# centraldb9.net
KiCad netlist of a schematic drawn in EAGLE
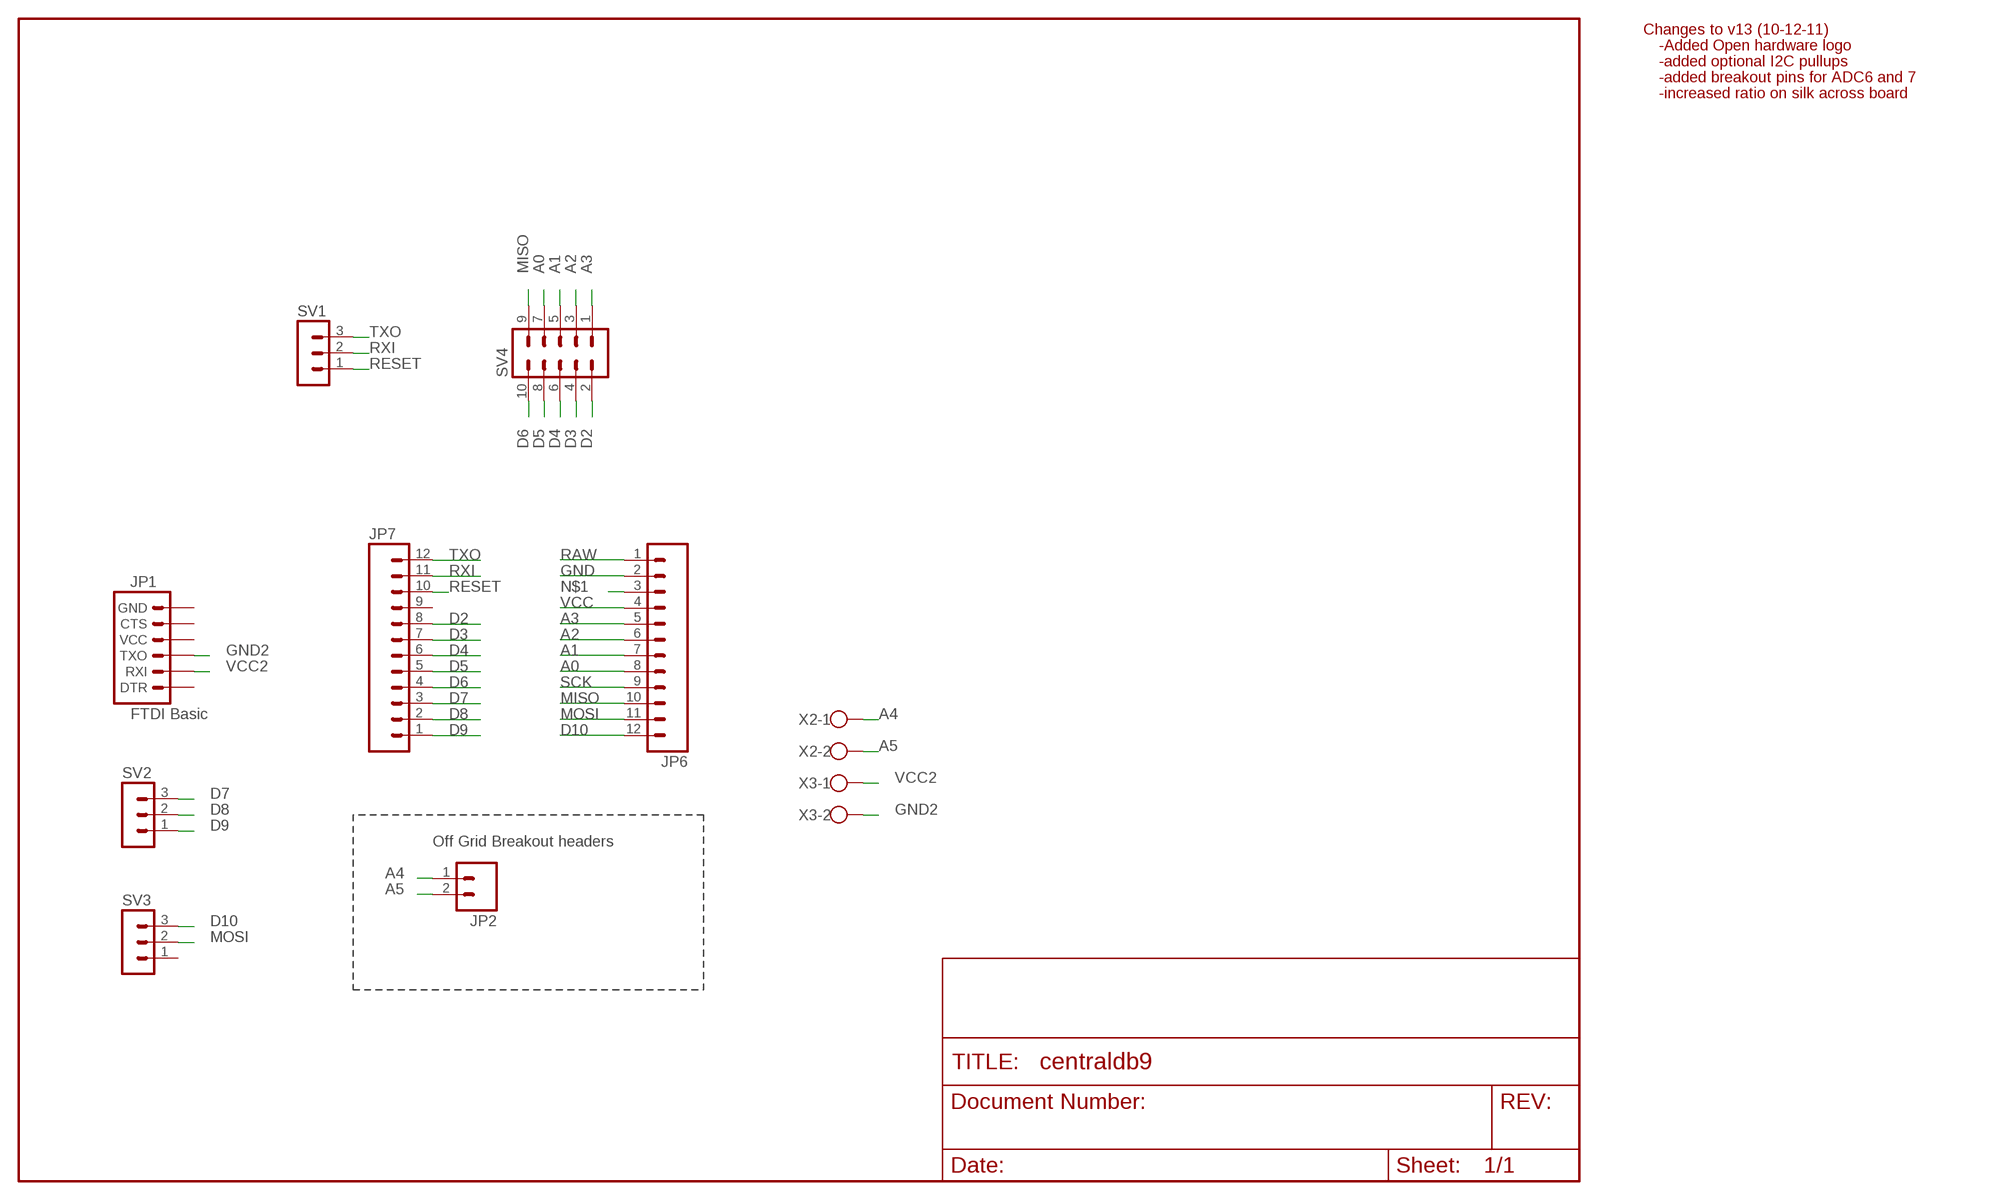
[diagram p0: schematic, sheet 1]

(export (version "E")
  (design (tool "Eeschema 10.0.6"))
  (components
    (comp (ref "JP1")
      (value "FTDI Basic")
      (footprint "eagle-import:1X06")
      (libsource (lib "eagle-import") (part "ARDUINO_SERIAL_PROGRAMPTH"))
    )
    (comp (ref "JP2")
      (value "M02PTH")
      (footprint "eagle-import:1X02")
      (libsource (lib "eagle-import") (part "M02PTH"))
    )
    (comp (ref "JP6")
      (value "M12PTH")
      (footprint "eagle-import:1X12")
      (libsource (lib "eagle-import") (part "M12PTH"))
    )
    (comp (ref "JP7")
      (value "M12PTH")
      (footprint "eagle-import:1X12")
      (libsource (lib "eagle-import") (part "M12PTH"))
    )
    (comp (ref "SV1")
      (value "MA03-1")
      (footprint "eagle-import:MA03-1")
      (libsource (lib "eagle-import") (part "MA03-1"))
    )
    (comp (ref "SV2")
      (value "MA03-1")
      (footprint "eagle-import:MA03-1")
      (libsource (lib "eagle-import") (part "MA03-1"))
    )
    (comp (ref "SV3")
      (value "MA03-1")
      (footprint "eagle-import:MA03-1")
      (libsource (lib "eagle-import") (part "MA03-1"))
    )
    (comp (ref "SV4")
      (value "MA05-2")
      (footprint "eagle-import:MA05-2")
      (libsource (lib "eagle-import") (part "MA05-2"))
    )
    (comp (ref "X2")
      (value "W237-102")
      (footprint "eagle-import:W237-102")
      (fields (field (name "MPN") "237-102"))
      (libsource (lib "eagle-import") (part "W237-102"))
    )
    (comp (ref "X3")
      (value "W237-102")
      (footprint "eagle-import:W237-102")
      (fields (field (name "MPN") "237-102"))
      (libsource (lib "eagle-import") (part "W237-102"))
    )
  )
  (nets
    (net (code "1") (name "/A0") (class "Default")
      (node (ref "JP6") (pin "8") (pinfunction "8_8") (pintype "passive"))
      (node (ref "SV4") (pin "7") (pinfunction "7_7") (pintype "passive"))
    )
    (net (code "2") (name "/A1") (class "Default")
      (node (ref "JP6") (pin "7") (pinfunction "7_7") (pintype "passive"))
      (node (ref "SV4") (pin "5") (pinfunction "5_5") (pintype "passive"))
    )
    (net (code "3") (name "/A2") (class "Default")
      (node (ref "JP6") (pin "6") (pinfunction "6_6") (pintype "passive"))
      (node (ref "SV4") (pin "3") (pinfunction "3_3") (pintype "passive"))
    )
    (net (code "4") (name "/A3") (class "Default")
      (node (ref "JP6") (pin "5") (pinfunction "5_5") (pintype "passive"))
      (node (ref "SV4") (pin "1") (pinfunction "1_1") (pintype "passive"))
    )
    (net (code "5") (name "/A4") (class "Default")
      (node (ref "JP2") (pin "1") (pinfunction "1_1") (pintype "passive"))
      (node (ref "X2") (pin "1") (pinfunction "KL_1") (pintype "passive"))
    )
    (net (code "6") (name "/A5") (class "Default")
      (node (ref "JP2") (pin "2") (pinfunction "2_2") (pintype "passive"))
      (node (ref "X2") (pin "2") (pinfunction "KL_2") (pintype "passive"))
    )
    (net (code "7") (name "/D2") (class "Default")
      (node (ref "JP7") (pin "8") (pinfunction "8_8") (pintype "passive"))
      (node (ref "SV4") (pin "2") (pinfunction "2_2") (pintype "passive"))
    )
    (net (code "8") (name "/D3") (class "Default")
      (node (ref "JP7") (pin "7") (pinfunction "7_7") (pintype "passive"))
      (node (ref "SV4") (pin "4") (pinfunction "4_4") (pintype "passive"))
    )
    (net (code "9") (name "/D4") (class "Default")
      (node (ref "JP7") (pin "6") (pinfunction "6_6") (pintype "passive"))
      (node (ref "SV4") (pin "6") (pinfunction "6_6") (pintype "passive"))
    )
    (net (code "10") (name "/D5") (class "Default")
      (node (ref "JP7") (pin "5") (pinfunction "5_5") (pintype "passive"))
      (node (ref "SV4") (pin "8") (pinfunction "8_8") (pintype "passive"))
    )
    (net (code "11") (name "/D6") (class "Default")
      (node (ref "JP7") (pin "4") (pinfunction "4_4") (pintype "passive"))
      (node (ref "SV4") (pin "10") (pinfunction "10_10") (pintype "passive"))
    )
    (net (code "12") (name "/D7") (class "Default")
      (node (ref "JP7") (pin "3") (pinfunction "3_3") (pintype "passive"))
      (node (ref "SV2") (pin "3") (pinfunction "3_3") (pintype "passive"))
    )
    (net (code "13") (name "/D8") (class "Default")
      (node (ref "JP7") (pin "2") (pinfunction "2_2") (pintype "passive"))
      (node (ref "SV2") (pin "2") (pinfunction "2_2") (pintype "passive"))
    )
    (net (code "14") (name "/D9") (class "Default")
      (node (ref "JP7") (pin "1") (pinfunction "1_1") (pintype "passive"))
      (node (ref "SV2") (pin "1") (pinfunction "1_1") (pintype "passive"))
    )
    (net (code "15") (name "/D10") (class "Default")
      (node (ref "JP6") (pin "12") (pinfunction "12_12") (pintype "passive"))
      (node (ref "SV3") (pin "3") (pinfunction "3_3") (pintype "passive"))
    )
    (net (code "16") (name "/GND") (class "Default")
      (node (ref "JP6") (pin "2") (pinfunction "2_2") (pintype "passive"))
    )
    (net (code "17") (name "/GND2") (class "Default")
      (node (ref "JP1") (pin "3") (pinfunction "TXO_3") (pintype "passive"))
      (node (ref "X3") (pin "2") (pinfunction "KL_2") (pintype "passive"))
    )
    (net (code "18") (name "/MISO") (class "Default")
      (node (ref "JP6") (pin "10") (pinfunction "10_10") (pintype "passive"))
      (node (ref "SV4") (pin "9") (pinfunction "9_9") (pintype "passive"))
    )
    (net (code "19") (name "/MOSI") (class "Default")
      (node (ref "JP6") (pin "11") (pinfunction "11_11") (pintype "passive"))
      (node (ref "SV3") (pin "2") (pinfunction "2_2") (pintype "passive"))
    )
    (net (code "20") (name "/N$1") (class "Default")
      (node (ref "JP6") (pin "3") (pinfunction "3_3") (pintype "passive"))
    )
    (net (code "21") (name "/RAW") (class "Default")
      (node (ref "JP6") (pin "1") (pinfunction "1_1") (pintype "passive"))
    )
    (net (code "22") (name "/RESET") (class "Default")
      (node (ref "JP7") (pin "10") (pinfunction "10_10") (pintype "passive"))
      (node (ref "SV1") (pin "1") (pinfunction "1_1") (pintype "passive"))
    )
    (net (code "23") (name "/RXI") (class "Default")
      (node (ref "JP7") (pin "11") (pinfunction "11_11") (pintype "passive"))
      (node (ref "SV1") (pin "2") (pinfunction "2_2") (pintype "passive"))
    )
    (net (code "24") (name "/SCK") (class "Default")
      (node (ref "JP6") (pin "9") (pinfunction "9_9") (pintype "passive"))
    )
    (net (code "25") (name "/TXO") (class "Default")
      (node (ref "JP7") (pin "12") (pinfunction "12_12") (pintype "passive"))
      (node (ref "SV1") (pin "3") (pinfunction "3_3") (pintype "passive"))
    )
    (net (code "26") (name "/VCC") (class "Default")
      (node (ref "JP6") (pin "4") (pinfunction "4_4") (pintype "passive"))
    )
    (net (code "27") (name "/VCC2") (class "Default")
      (node (ref "JP1") (pin "2") (pinfunction "RXI_2") (pintype "passive"))
      (node (ref "X3") (pin "1") (pinfunction "KL_1") (pintype "passive"))
    )
    (net (code "28") (name "unconnected-(JP1-CTS-Pad5)") (class "Default")
      (node (ref "JP1") (pin "5") (pinfunction "CTS_5") (pintype "passive"))
    )
    (net (code "29") (name "unconnected-(JP1-DTR-Pad1)") (class "Default")
      (node (ref "JP1") (pin "1") (pinfunction "DTR_1") (pintype "passive"))
    )
    (net (code "30") (name "unconnected-(JP1-GND-Pad6)") (class "Default")
      (node (ref "JP1") (pin "6") (pinfunction "GND_6") (pintype "passive"))
    )
    (net (code "31") (name "unconnected-(JP1-VCC-Pad4)") (class "Default")
      (node (ref "JP1") (pin "4") (pinfunction "VCC_4") (pintype "passive"))
    )
    (net (code "32") (name "unconnected-(JP7-Pad9)") (class "Default")
      (node (ref "JP7") (pin "9") (pinfunction "9_9") (pintype "passive"))
    )
    (net (code "33") (name "unconnected-(SV3-Pad1)") (class "Default")
      (node (ref "SV3") (pin "1") (pinfunction "1_1") (pintype "passive"))
    )
  )
)
